# 51-2001-01-7_04_Power_Module_Schematic.net
KiCad netlist of a schematic drawn in Altium Designer
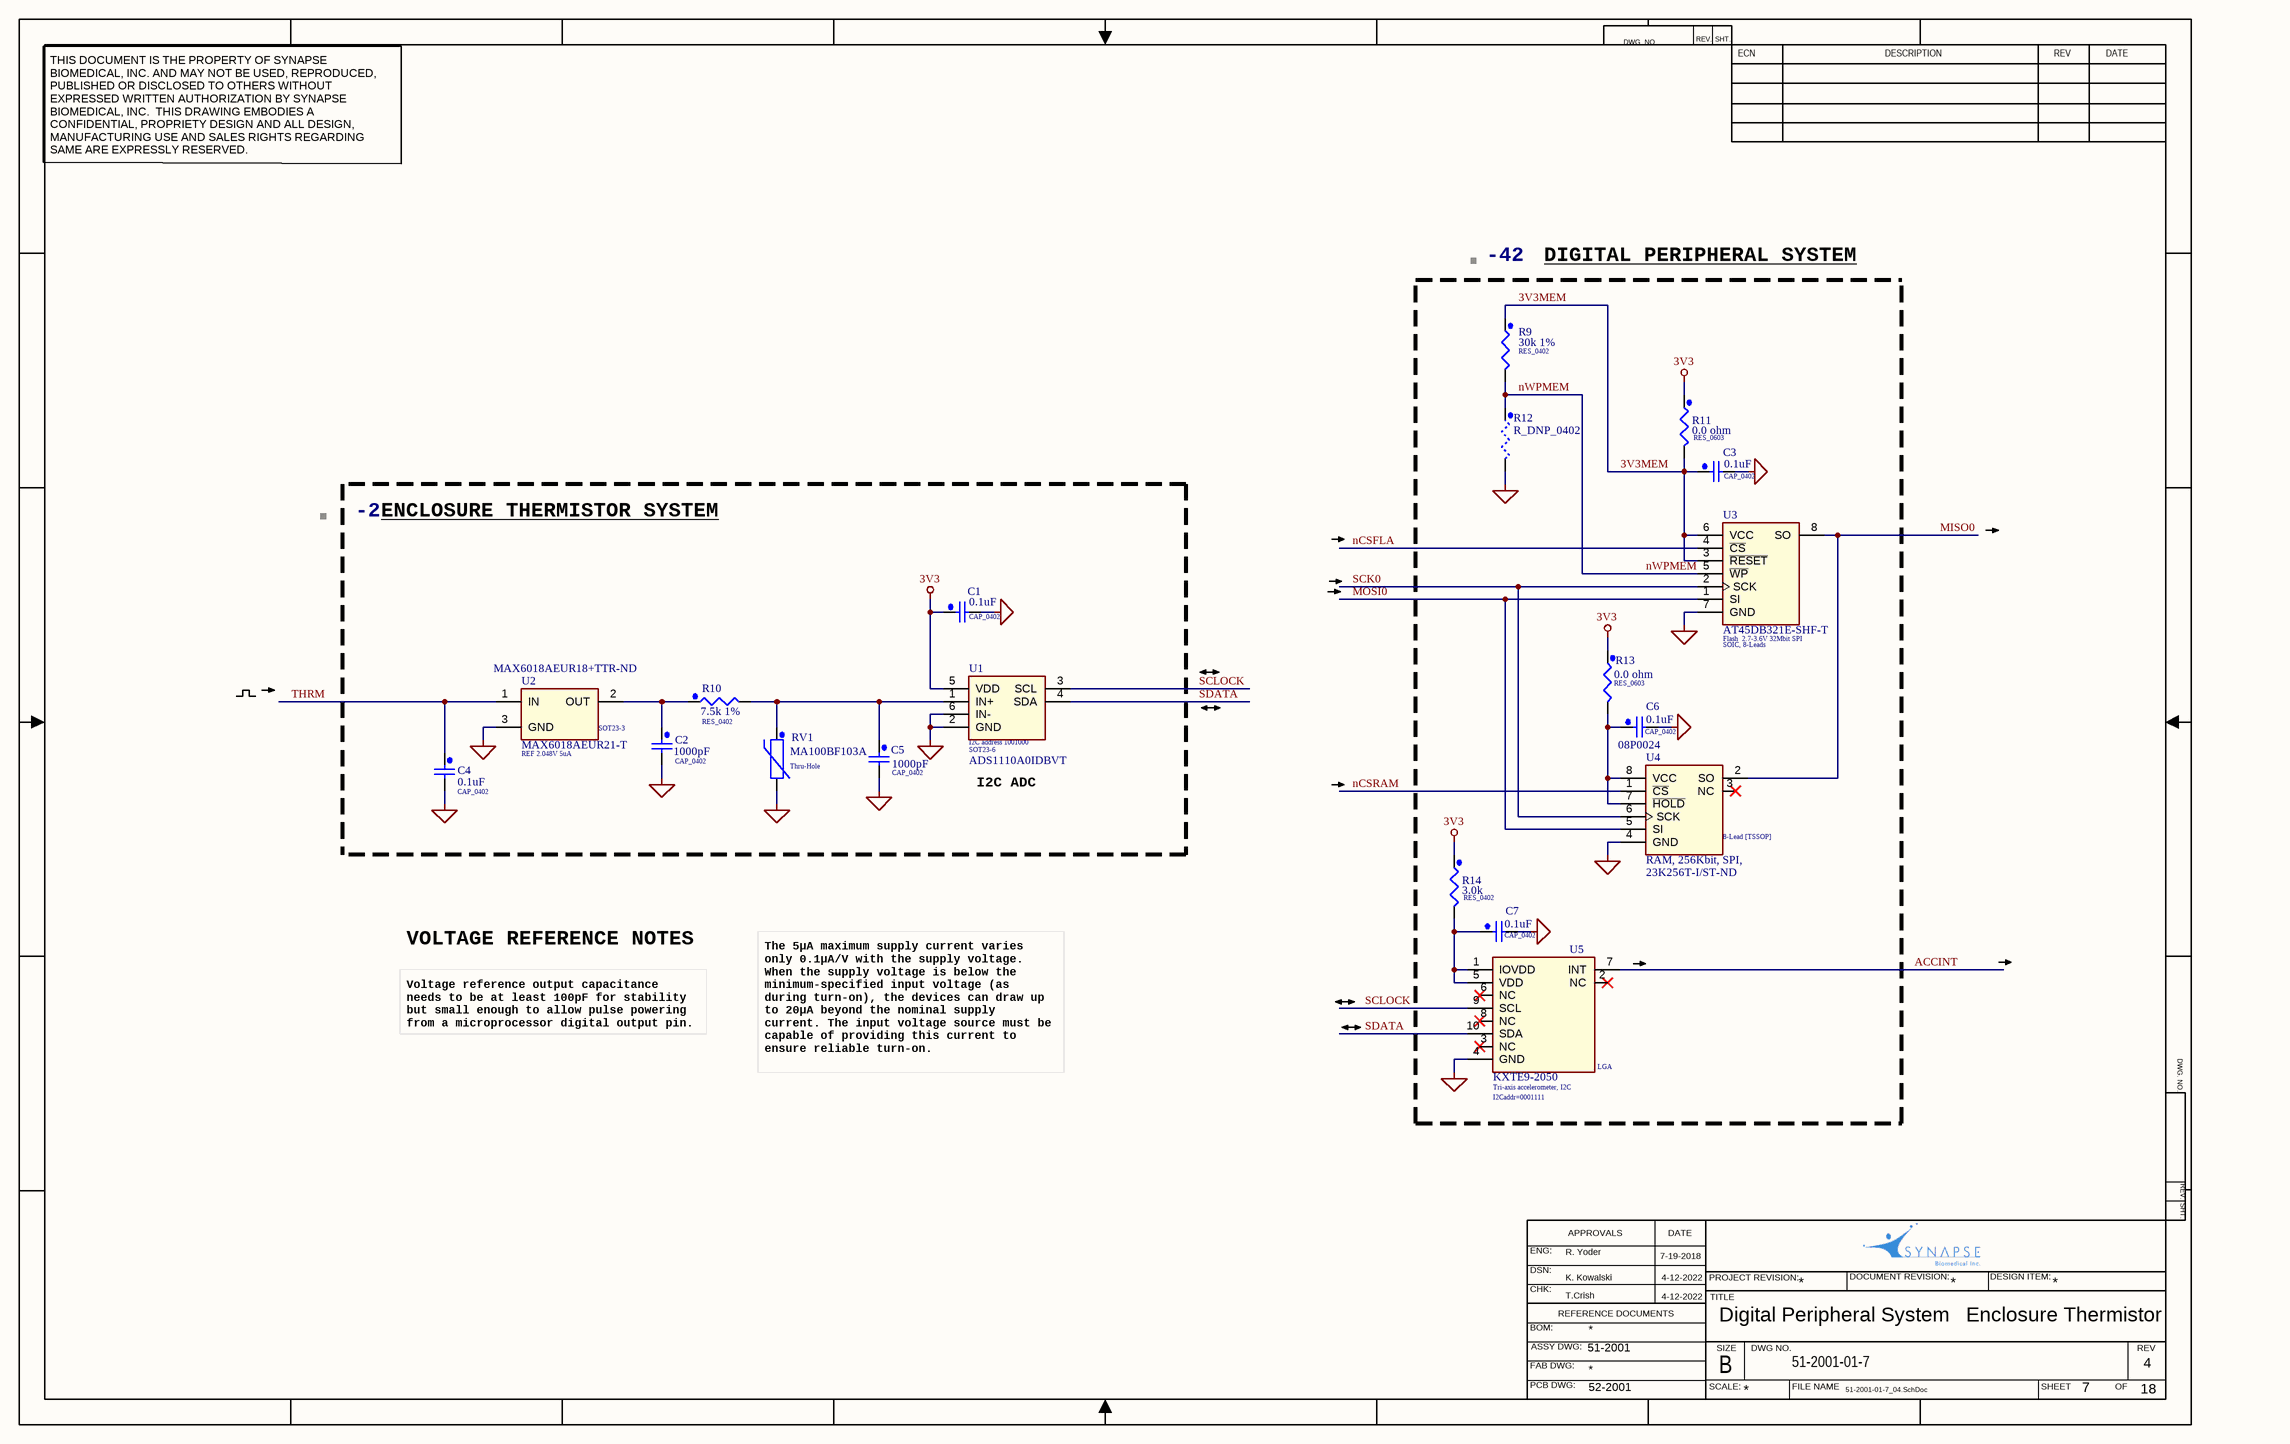
[diagram p0: 51-2001-01-7_04 Power Module Schematic.SchDoc]

(export (version "E")
  (design (tool "Eeschema 10.0.6"))
  (components
    (comp (ref "-2")
      (value "BOM_S1")
      (description "BOM item small graphic")
      (fields (field (name "XDESCRIPTION") "ENCLOSURE THERMISTOR SYSTEM"))
      (libsource (lib "BOM_sym") (part "BOM_S1"))
    )
    (comp (ref "-42")
      (value "BOM_S1")
      (description "BOM item small graphic")
      (fields (field (name "XDESCRIPTION") "DIGITAL PERIPHERAL SYSTEM"))
      (libsource (lib "BOM_sym") (part "BOM_S1"))
    )
    (comp (ref "C1")
      (value "0.1uF")
      (footprint "CAP_0402")
      (description "0.1uF, 16V, X7R, 0402, RoHS")
      (fields
        (field (name "MFR") "Murata")
        (field (name "PACKAGEDESCRIPTION") "CAP_0402")
        (field (name "MPN") "GRM155R71C104KA88D")
      )
      (libsource (lib "NNPS Integrated Parts") (part "GRM155R71C104KA88D"))
    )
    (comp (ref "C2")
      (value "1000pF")
      (footprint "CAP_0402")
      (description "1000pF, 50V, C0G, 5%, 0402, RoHS")
      (fields
        (field (name "MFR") "Murata")
        (field (name "PACKAGEDESCRIPTION") "CAP_0402")
        (field (name "MPN") "GRM1555C1H102JA01D")
      )
      (libsource (lib "NNPS Integrated Parts") (part "GRM1555C1H102JA01D"))
    )
    (comp (ref "C3")
      (value "0.1uF")
      (footprint "CAP_0402")
      (description "0.1uF, 16V, X7R, 0402, RoHS")
      (fields
        (field (name "MFR") "Murata")
        (field (name "PACKAGEDESCRIPTION") "CAP_0402")
        (field (name "MPN") "GRM155R71C104KA88D")
      )
      (libsource (lib "NNPS Integrated Parts") (part "GRM155R71C104KA88D"))
    )
    (comp (ref "C4")
      (value "0.1uF")
      (footprint "CAP_0402")
      (description "0.1uF, 16V, X7R, 0402, RoHS")
      (fields
        (field (name "MFR") "Murata")
        (field (name "PACKAGEDESCRIPTION") "CAP_0402")
        (field (name "MPN") "GRM155R71C104KA88D")
      )
      (libsource (lib "NNPS Integrated Parts") (part "GRM155R71C104KA88D"))
    )
    (comp (ref "C5")
      (value "1000pF")
      (footprint "CAP_0402")
      (description "1000pF, 50V, C0G, 5%, 0402, RoHS")
      (fields
        (field (name "MFR") "Murata")
        (field (name "PACKAGEDESCRIPTION") "CAP_0402")
        (field (name "MPN") "GRM1555C1H102JA01D")
      )
      (libsource (lib "NNPS Integrated Parts") (part "GRM1555C1H102JA01D"))
    )
    (comp (ref "C6")
      (value "0.1uF")
      (footprint "CAP_0402")
      (description "0.1uF, 16V, X7R, 0402, RoHS")
      (fields
        (field (name "MFR") "Murata")
        (field (name "PACKAGEDESCRIPTION") "CAP_0402")
        (field (name "MPN") "GRM155R71C104KA88D")
      )
      (libsource (lib "NNPS Integrated Parts") (part "GRM155R71C104KA88D"))
    )
    (comp (ref "C7")
      (value "0.1uF")
      (footprint "CAP_0402")
      (description "0.1uF, 16V, X7R, 0402, RoHS")
      (fields
        (field (name "MFR") "Murata")
        (field (name "PACKAGEDESCRIPTION") "CAP_0402")
        (field (name "MPN") "GRM155R71C104KA88D")
      )
      (libsource (lib "NNPS Integrated Parts") (part "GRM155R71C104KA88D"))
    )
    (comp (ref "R9")
      (value "30k 1%")
      (footprint "RES_0402")
      (description "30k ohm, 1%, 1/16W, 0402, RoHS")
      (fields
        (field (name "MFR") "Vishay Dale")
        (field (name "PACKAGEDESCRIPTION") "RES_0402")
        (field (name "MPN") "CRCW040230K0FKED")
      )
      (libsource (lib "NNPS Integrated Parts") (part "MCR01MZPF3002"))
    )
    (comp (ref "R10")
      (value "7.5k 1%")
      (footprint "RES_0402")
      (description "7.5k ohm, 1%, 1/16W, 0402, RoHS")
      (fields
        (field (name "MFR") "Vishay Dale")
        (field (name "PACKAGEDESCRIPTION") "RES_0402")
        (field (name "MPN") "TNPW04027K50BEED")
      )
      (libsource (lib "NNPS Integrated Parts") (part "TNPW04027K50BEED"))
    )
    (comp (ref "R11")
      (value "0.0 ohm")
      (footprint "RES_0603")
      (description "0.0 ohm, 1/16W, 0603, RoHS")
      (fields
        (field (name "MFR") "Vishay Dale")
        (field (name "PACKAGEDESCRIPTION") "RES_0603")
        (field (name "MPN") "CRCW06030000Z0EA")
      )
      (libsource (lib "NNPS Integrated Parts") (part "MCR03ERTJ000"))
    )
    (comp (ref "R12")
      (value "R_DNP_0402")
      (footprint "RES_0402")
      (description "DO NOT POPULATE")
      (libsource (lib "NNPS Integrated Parts") (part "R_DNP_0402"))
    )
    (comp (ref "R13")
      (value "0.0 ohm")
      (footprint "RES_0603")
      (description "0.0 ohm, 1/16W, 0603, RoHS")
      (fields
        (field (name "MFR") "Vishay Dale")
        (field (name "PACKAGEDESCRIPTION") "RES_0603")
        (field (name "MPN") "CRCW06030000Z0EA")
      )
      (libsource (lib "NNPS Integrated Parts") (part "MCR03ERTJ000"))
    )
    (comp (ref "R14")
      (value "3.0k")
      (footprint "RES_0603")
      (description "3.0k ohm, 1/16W, 0603, RoHS")
      (fields
        (field (name "MFR") "Vishay Dale")
        (field (name "PACKAGEDESCRIPTION") "RES_0402")
        (field (name "MPN") "CRCW04023K00FKEDHP")
      )
      (libsource (lib "NNPS Integrated Parts") (part "MCR03ERTJ000"))
    )
    (comp (ref "RV1")
      (value "Thermistor 10k radial NTC")
      (footprint "NTC")
      (description "Thermistor, 10k, radial, NTC, RoHS")
      (fields
        (field (name "MFR") "Amphenol Advanced Sensors")
        (field (name "PACKAGEDESCRIPTION") "Thru-Hole")
        (field (name "MPN") "MA100BF103A")
      )
      (libsource (lib "NNPS Integrated Parts") (part "RT_10k_rad"))
    )
    (comp (ref "U1")
      (value "ADC 16bit I2C")
      (footprint "SOT23-6")
      (description "ADC, 16bit, I2C, SOT23-6, RoHS")
      (fields
        (field (name "MFR") "Texas Instruments")
        (field (name "NOTE") "I2C address 1001000")
        (field (name "PACKAGEDESCRIPTION") "SOT23-6")
        (field (name "MPN") "ADS1110A0IDBVT")
      )
      (libsource (lib "NNPS Integrated Parts") (part "ADS1110A0IDBV"))
    )
    (comp (ref "U2")
      (value "REF 2.048V 5uA")
      (footprint "SOT23-3")
      (description "Ref, 2.048V, 5uA, SOT23-3, RoHS")
      (fields
        (field (name "PACKAGEDESCRIPTION") "SOT23-3")
        (field (name "MFR") "Maxim Integrated")
        (field (name "MPN") "MAX6018AEUR21-T")
        (field (name "SUPPLIER PART NUMBER 2") "MAX6018AEUR18+TTR-ND")
      )
      (libsource (lib "NNPS Integrated Parts") (part "MAX6018AEUR21-T"))
    )
    (comp (ref "U3")
      (value "Flash  2.7-3.6V 32Mbit SPI")
      (footprint "DFN8")
      (description "Flash, 32Mbit, SPI, SO8")
      (fields
        (field (name "MFR") "Adesto Technologies")
        (field (name "PACKAGEDESCRIPTION") "SOIC, 8-Leads")
        (field (name "MPN") "AT45DB321E-SHF-T")
      )
      (libsource (lib "NNPS Integrated Parts") (part "AT45DB321D-SU"))
    )
    (comp (ref "U4")
      (value "RAM, 256Kbit, SPI,")
      (footprint "TSSOP-8L")
      (description "RAM, 256Kbit, SPI, TSSOP8, RoHS")
      (fields
        (field (name "PACKAGEDESCRIPTION") "8-Lead [TSSOP]")
        (field (name "MFR") "MicroChip Technology")
        (field (name "MPN") "23K256T-I/ST-ND")
        (field (name "SUPPLIER PART NUMBER 2") "08P0024")
      )
      (libsource (lib "NNPS Integrated Parts") (part "23K256T-I/ST"))
    )
    (comp (ref "U5")
      (value "Tri-axis accelerometer, I2C")
      (footprint "lga10")
      (description "Tri-axis accelerometer, I2C,  LGA10, RoHS")
      (fields
        (field (name "MFR") "Kionix")
        (field (name "PACKAGEDESCRIPTION") "LGA")
        (field (name "NOTE") "I2Caddr=0001111")
        (field (name "MPN") "KXTE9-2050")
      )
      (libsource (lib "NNPS Integrated Parts") (part "KXTE9-2050"))
    )
  )
  (nets
    (net (code "1") (name "/3V3MEM") (class "Default")
      (node (ref "C3") (pin "1") (pinfunction "1_1") (pintype "passive"))
      (node (ref "R11") (pin "2") (pinfunction "2_2") (pintype "passive"))
      (node (ref "R9") (pin "1") (pinfunction "1_1") (pintype "passive"))
      (node (ref "U3") (pin "3") (pinfunction "RESET_3") (pintype "passive"))
      (node (ref "U3") (pin "6") (pinfunction "VCC_6") (pintype "passive"))
    )
    (net (code "2") (name "/ACCINT") (class "Default")
      (node (ref "U5") (pin "7") (pinfunction "INT_7") (pintype "passive"))
    )
    (net (code "3") (name "/MISO0") (class "Default")
      (node (ref "U3") (pin "8") (pinfunction "SO_8") (pintype "passive"))
      (node (ref "U4") (pin "2") (pinfunction "SO_2") (pintype "passive"))
    )
    (net (code "4") (name "/MOSI0") (class "Default")
      (node (ref "U3") (pin "1") (pinfunction "SI_1") (pintype "passive"))
      (node (ref "U4") (pin "5") (pinfunction "SI_5") (pintype "passive"))
    )
    (net (code "5") (name "/SCK0") (class "Default")
      (node (ref "U3") (pin "2") (pinfunction "SCK_2") (pintype "passive"))
      (node (ref "U4") (pin "6") (pinfunction "SCK_6") (pintype "passive"))
    )
    (net (code "6") (name "/SCLOCK") (class "Default")
      (node (ref "U1") (pin "3") (pinfunction "SCL_3") (pintype "passive"))
      (node (ref "U5") (pin "9") (pinfunction "SCL_9") (pintype "passive"))
    )
    (net (code "7") (name "/SDATA") (class "Default")
      (node (ref "U1") (pin "4") (pinfunction "SDA_4") (pintype "passive"))
      (node (ref "U5") (pin "10") (pinfunction "SDA_10") (pintype "passive"))
    )
    (net (code "8") (name "/THRM") (class "Default")
      (node (ref "C4") (pin "1") (pinfunction "1_1") (pintype "passive"))
      (node (ref "U2") (pin "1") (pinfunction "IN_1") (pintype "passive"))
    )
    (net (code "9") (name "/nCSFLA") (class "Default")
      (node (ref "U3") (pin "4") (pinfunction "CS_4") (pintype "passive"))
    )
    (net (code "10") (name "/nCSRAM") (class "Default")
      (node (ref "U4") (pin "1") (pinfunction "~{CS}_1") (pintype "passive"))
    )
    (net (code "11") (name "/nWPMEM") (class "Default")
      (node (ref "R12") (pin "1") (pinfunction "1_1") (pintype "passive"))
      (node (ref "R9") (pin "2") (pinfunction "2_2") (pintype "passive"))
      (node (ref "U3") (pin "5") (pinfunction "WP_5") (pintype "passive"))
    )
    (net (code "12") (name "3V3") (class "Default")
      (node (ref "C1") (pin "1") (pinfunction "1_1") (pintype "passive"))
      (node (ref "R11") (pin "1") (pinfunction "1_1") (pintype "passive"))
      (node (ref "R13") (pin "1") (pinfunction "1_1") (pintype "passive"))
      (node (ref "R14") (pin "1") (pinfunction "1_1") (pintype "passive"))
      (node (ref "U1") (pin "5") (pinfunction "VDD_5") (pintype "passive"))
    )
    (net (code "13") (name "GND") (class "Default")
      (node (ref "C1") (pin "2") (pinfunction "2_2") (pintype "passive"))
      (node (ref "C2") (pin "2") (pinfunction "2_2") (pintype "passive"))
      (node (ref "C3") (pin "2") (pinfunction "2_2") (pintype "passive"))
      (node (ref "C4") (pin "2") (pinfunction "2_2") (pintype "passive"))
      (node (ref "C5") (pin "2") (pinfunction "2_2") (pintype "passive"))
      (node (ref "C6") (pin "2") (pinfunction "2_2") (pintype "passive"))
      (node (ref "C7") (pin "2") (pinfunction "2_2") (pintype "passive"))
      (node (ref "R12") (pin "2") (pinfunction "2_2") (pintype "passive"))
      (node (ref "RV1") (pin "2") (pinfunction "2_2") (pintype "passive"))
      (node (ref "U1") (pin "2") (pinfunction "GND_2") (pintype "passive"))
      (node (ref "U1") (pin "6") (pinfunction "IN-_6") (pintype "passive"))
      (node (ref "U2") (pin "3") (pinfunction "GND_3") (pintype "passive"))
      (node (ref "U3") (pin "7") (pinfunction "GND_7") (pintype "passive"))
      (node (ref "U4") (pin "4") (pinfunction "GND_4") (pintype "passive"))
      (node (ref "U5") (pin "4") (pinfunction "GND_4") (pintype "passive"))
    )
    (net (code "14") (name "Net-(U1-IN+)") (class "Default")
      (node (ref "C5") (pin "1") (pinfunction "1_1") (pintype "passive"))
      (node (ref "R10") (pin "2") (pinfunction "2_2") (pintype "passive"))
      (node (ref "RV1") (pin "1") (pinfunction "1_1") (pintype "passive"))
      (node (ref "U1") (pin "1") (pinfunction "IN+_1") (pintype "passive"))
    )
    (net (code "15") (name "Net-(U2-OUT)") (class "Default")
      (node (ref "C2") (pin "1") (pinfunction "1_1") (pintype "passive"))
      (node (ref "R10") (pin "1") (pinfunction "1_1") (pintype "passive"))
      (node (ref "U2") (pin "2") (pinfunction "OUT_2") (pintype "passive"))
    )
    (net (code "16") (name "Net-(U4-VCC)") (class "Default")
      (node (ref "C6") (pin "1") (pinfunction "1_1") (pintype "passive"))
      (node (ref "R13") (pin "2") (pinfunction "2_2") (pintype "passive"))
      (node (ref "U4") (pin "7") (pinfunction "~{HOLD}_7") (pintype "passive"))
      (node (ref "U4") (pin "8") (pinfunction "VCC_8") (pintype "passive"))
    )
    (net (code "17") (name "Net-(U5-IOVDD)") (class "Default")
      (node (ref "C7") (pin "1") (pinfunction "1_1") (pintype "passive"))
      (node (ref "R14") (pin "2") (pinfunction "2_2") (pintype "passive"))
      (node (ref "U5") (pin "1") (pinfunction "IOVDD_1") (pintype "passive"))
      (node (ref "U5") (pin "5") (pinfunction "VDD_5") (pintype "passive"))
    )
    (net (code "18") (name "unconnected-(U4-NC-Pad3)") (class "Default")
      (node (ref "U4") (pin "3") (pinfunction "NC_3") (pintype "passive+no_connect"))
    )
    (net (code "19") (name "unconnected-(U5-NC-Pad2)") (class "Default")
      (node (ref "U5") (pin "2") (pinfunction "NC_2") (pintype "power_in+no_connect"))
    )
    (net (code "20") (name "unconnected-(U5-NC-Pad3)") (class "Default")
      (node (ref "U5") (pin "3") (pinfunction "NC_3") (pintype "passive+no_connect"))
    )
    (net (code "21") (name "unconnected-(U5-NC-Pad6)") (class "Default")
      (node (ref "U5") (pin "6") (pinfunction "NC_6") (pintype "passive+no_connect"))
    )
    (net (code "22") (name "unconnected-(U5-NC-Pad8)") (class "Default")
      (node (ref "U5") (pin "8") (pinfunction "NC_8") (pintype "passive+no_connect"))
    )
  )
)
